# LED.net
KiCad netlist of a schematic drawn in Altium Designer
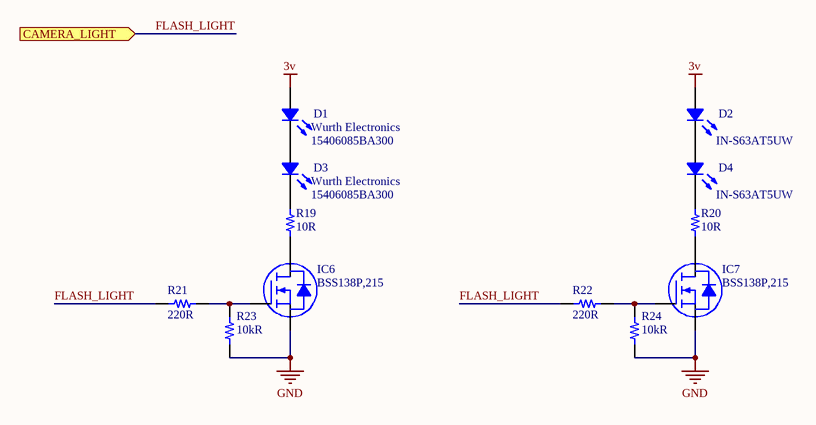
[diagram p0: LED.SchDoc]

(export (version "E")
  (design (tool "Eeschema 10.0.6"))
  (components
    (comp (ref "D1")
      (value "15406085BA300")
      (footprint "LED 0603/1608")
      (description "Chip LED")
      (fields (field (name "MANUFACTURER") "Wurth Electronics"))
      (libsource (lib "yildizIoT Library") (part "LED"))
    )
    (comp (ref "D2")
      (value "IN-S63AT5UW")
      (footprint "LED 0603/1608")
      (description "Chip LED")
      (fields (field (name "MANUFACTURER") "Inolux"))
      (libsource (lib "yildizIoT Library") (part "LED"))
    )
    (comp (ref "D3")
      (value "15406085BA300")
      (footprint "LED 0603/1608")
      (description "Chip LED")
      (fields (field (name "MANUFACTURER") "Wurth Electronics"))
      (libsource (lib "yildizIoT Library") (part "LED"))
    )
    (comp (ref "D4")
      (value "IN-S63AT5UW")
      (footprint "LED 0603/1608")
      (description "Chip LED")
      (fields (field (name "MANUFACTURER") "Inolux"))
      (libsource (lib "yildizIoT Library") (part "LED"))
    )
    (comp (ref "IC6")
      (value "BSS138P,215")
      (footprint "DIODES SOT-23-3")
      (description "MOSFET N-CH 50V 200MA SOT23-3")
      (fields (field (name "MANUFACTURER") "Nexperia"))
      (libsource (lib "Celestial Altium Library - altium_library") (part "DIODES INC MOSFET N-CH SOT-23-3"))
    )
    (comp (ref "IC7")
      (value "BSS138P,215")
      (footprint "DIODES SOT-23-3")
      (description "MOSFET N-CH 50V 200MA SOT23-3")
      (fields (field (name "MANUFACTURER") "Nexperia"))
      (libsource (lib "Celestial Altium Library - altium_library") (part "DIODES INC MOSFET N-CH SOT-23-3"))
    )
    (comp (ref "R19")
      (value "10R")
      (footprint "RES 0603/1608")
      (description "Ceramic, SMT Capacitor")
      (fields
        (field (name "MANUFACTURER") "Yageo")
        (field (name "MANUFACTURER PART NUMBER") "RC0603FR-0710RL")
      )
      (libsource (lib "yildizIoT Library") (part "Resistor_Chip"))
    )
    (comp (ref "R20")
      (value "10R")
      (footprint "RES 0603/1608")
      (description "Ceramic, SMT Capacitor")
      (fields
        (field (name "MANUFACTURER") "Yageo")
        (field (name "MANUFACTURER PART NUMBER") "RC0603FR-0710RL")
      )
      (libsource (lib "yildizIoT Library") (part "Resistor_Chip"))
    )
    (comp (ref "R21")
      (value "220R")
      (footprint "RES 0603/1608")
      (description "Ceramic, SMT Capacitor")
      (fields
        (field (name "MANUFACTURER") "Yageo")
        (field (name "MANUFACTURER PART NUMBER") "RC0603FR-07220RL")
      )
      (libsource (lib "yildizIoT Library") (part "Resistor_Chip"))
    )
    (comp (ref "R22")
      (value "220R")
      (footprint "RES 0603/1608")
      (description "Ceramic, SMT Capacitor")
      (fields
        (field (name "MANUFACTURER") "Yageo")
        (field (name "MANUFACTURER PART NUMBER") "RC0603FR-07220RL")
      )
      (libsource (lib "yildizIoT Library") (part "Resistor_Chip"))
    )
    (comp (ref "R23")
      (value "10kR")
      (footprint "RES 0603/1608")
      (description "Ceramic, SMT Capacitor")
      (fields
        (field (name "MANUFACTURER") "Stackpole Electronics")
        (field (name "MANUFACTURER PART NUMBER") "RNCP0603FTD10K0")
      )
      (libsource (lib "yildizIoT Library") (part "Resistor_Chip"))
    )
    (comp (ref "R24")
      (value "10kR")
      (footprint "RES 0603/1608")
      (description "Ceramic, SMT Capacitor")
      (fields
        (field (name "MANUFACTURER") "Stackpole Electronics")
        (field (name "MANUFACTURER PART NUMBER") "RNCP0603FTD10K0")
      )
      (libsource (lib "yildizIoT Library") (part "Resistor_Chip"))
    )
  )
  (nets
    (net (code "1") (name "/FLASH_LIGHT") (class "Default")
      (node (ref "R21") (pin "1") (pinfunction "1_1") (pintype "passive"))
      (node (ref "R22") (pin "1") (pinfunction "1_1") (pintype "passive"))
    )
    (net (code "2") (name "3v") (class "Default")
      (node (ref "D1") (pin "1") (pinfunction "1_1") (pintype "passive"))
      (node (ref "D2") (pin "1") (pinfunction "1_1") (pintype "passive"))
    )
    (net (code "3") (name "GND") (class "Default")
      (node (ref "IC6") (pin "2") (pinfunction "S_2") (pintype "passive"))
      (node (ref "IC7") (pin "2") (pinfunction "S_2") (pintype "passive"))
      (node (ref "R23") (pin "2") (pinfunction "2_2") (pintype "passive"))
      (node (ref "R24") (pin "2") (pinfunction "2_2") (pintype "passive"))
    )
    (net (code "4") (name "Net-(D1-Pad2)") (class "Default")
      (node (ref "D1") (pin "2") (pinfunction "2_2") (pintype "passive"))
      (node (ref "D3") (pin "1") (pinfunction "1_1") (pintype "passive"))
    )
    (net (code "5") (name "Net-(D2-Pad2)") (class "Default")
      (node (ref "D2") (pin "2") (pinfunction "2_2") (pintype "passive"))
      (node (ref "D4") (pin "1") (pinfunction "1_1") (pintype "passive"))
    )
    (net (code "6") (name "Net-(D3-Pad2)") (class "Default")
      (node (ref "D3") (pin "2") (pinfunction "2_2") (pintype "passive"))
      (node (ref "R19") (pin "2") (pinfunction "2_2") (pintype "passive"))
    )
    (net (code "7") (name "Net-(D4-Pad2)") (class "Default")
      (node (ref "D4") (pin "2") (pinfunction "2_2") (pintype "passive"))
      (node (ref "R20") (pin "2") (pinfunction "2_2") (pintype "passive"))
    )
    (net (code "8") (name "Net-(IC6-D)") (class "Default")
      (node (ref "IC6") (pin "3") (pinfunction "D_3") (pintype "passive"))
      (node (ref "R19") (pin "1") (pinfunction "1_1") (pintype "passive"))
    )
    (net (code "9") (name "Net-(IC6-G)") (class "Default")
      (node (ref "IC6") (pin "1") (pinfunction "G_1") (pintype "passive"))
      (node (ref "R21") (pin "2") (pinfunction "2_2") (pintype "passive"))
      (node (ref "R23") (pin "1") (pinfunction "1_1") (pintype "passive"))
    )
    (net (code "10") (name "Net-(IC7-D)") (class "Default")
      (node (ref "IC7") (pin "3") (pinfunction "D_3") (pintype "passive"))
      (node (ref "R20") (pin "1") (pinfunction "1_1") (pintype "passive"))
    )
    (net (code "11") (name "Net-(IC7-G)") (class "Default")
      (node (ref "IC7") (pin "1") (pinfunction "G_1") (pintype "passive"))
      (node (ref "R22") (pin "2") (pinfunction "2_2") (pintype "passive"))
      (node (ref "R24") (pin "1") (pinfunction "1_1") (pintype "passive"))
    )
  )
)
